# Sheetchanging.net
KiCad netlist of a schematic drawn in Altium Designer
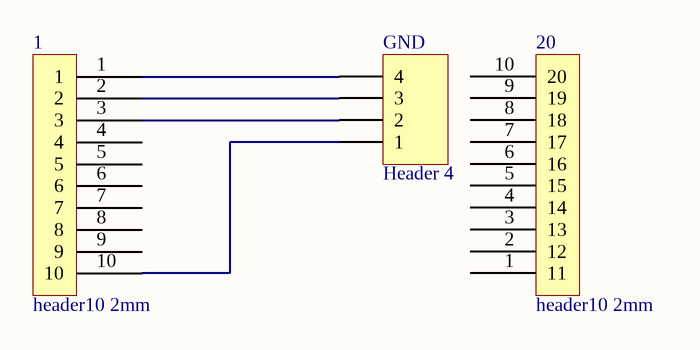
[diagram p0: Sheetchanging.SchDoc]

(export (version "E")
  (design (tool "Eeschema 10.0.6"))
  (components
    (comp (ref "1")
      (value "header10 2mm")
      (footprint "header10 2mm big")
      (libsource (lib "") (part "header10 2mm_1"))
    )
    (comp (ref "20")
      (value "header10 2mm")
      (footprint "header10 2mm big")
      (libsource (lib "My Sch Library") (part "header10 2mm"))
    )
    (comp (ref "GND")
      (value "Header 4")
      (footprint "HDR1X4")
      (description "Header, 4-Pin")
      (fields (field (name "PUBLISHER") "Altium Limited"))
      (libsource (lib "My Sch Library") (part "Header 4"))
    )
  )
  (nets
    (net (code "1") (name "Net-(1-Pad1)") (class "Default")
      (node (ref "1") (pin "1") (pinfunction "1_1") (pintype "passive"))
      (node (ref "GND") (pin "4") (pinfunction "4_4") (pintype "passive"))
    )
    (net (code "2") (name "Net-(1-Pad2)") (class "Default")
      (node (ref "1") (pin "2") (pinfunction "2_2") (pintype "passive"))
      (node (ref "GND") (pin "3") (pinfunction "3_3") (pintype "passive"))
    )
    (net (code "3") (name "Net-(1-Pad3)") (class "Default")
      (node (ref "1") (pin "3") (pinfunction "3_3") (pintype "passive"))
      (node (ref "GND") (pin "2") (pinfunction "2_2") (pintype "passive"))
    )
    (net (code "4") (name "Net-(1-Pad10)") (class "Default")
      (node (ref "1") (pin "10") (pinfunction "10_10") (pintype "passive"))
      (node (ref "GND") (pin "1") (pinfunction "1_1") (pintype "passive"))
    )
    (net (code "5") (name "unconnected-(1-Pad4)") (class "Default")
      (node (ref "1") (pin "4") (pinfunction "4_4") (pintype "passive"))
    )
    (net (code "6") (name "unconnected-(1-Pad5)") (class "Default")
      (node (ref "1") (pin "5") (pinfunction "5_5") (pintype "passive"))
    )
    (net (code "7") (name "unconnected-(1-Pad6)") (class "Default")
      (node (ref "1") (pin "6") (pinfunction "6_6") (pintype "passive"))
    )
    (net (code "8") (name "unconnected-(1-Pad7)") (class "Default")
      (node (ref "1") (pin "7") (pinfunction "7_7") (pintype "passive"))
    )
    (net (code "9") (name "unconnected-(1-Pad8)") (class "Default")
      (node (ref "1") (pin "8") (pinfunction "8_8") (pintype "passive"))
    )
    (net (code "10") (name "unconnected-(1-Pad9)") (class "Default")
      (node (ref "1") (pin "9") (pinfunction "9_9") (pintype "passive"))
    )
    (net (code "11") (name "unconnected-(20-11-Pad1)") (class "Default")
      (node (ref "20") (pin "1") (pinfunction "11_1") (pintype "passive"))
    )
    (net (code "12") (name "unconnected-(20-12-Pad2)") (class "Default")
      (node (ref "20") (pin "2") (pinfunction "12_2") (pintype "passive"))
    )
    (net (code "13") (name "unconnected-(20-13-Pad3)") (class "Default")
      (node (ref "20") (pin "3") (pinfunction "13_3") (pintype "passive"))
    )
    (net (code "14") (name "unconnected-(20-14-Pad4)") (class "Default")
      (node (ref "20") (pin "4") (pinfunction "14_4") (pintype "passive"))
    )
    (net (code "15") (name "unconnected-(20-15-Pad5)") (class "Default")
      (node (ref "20") (pin "5") (pinfunction "15_5") (pintype "passive"))
    )
    (net (code "16") (name "unconnected-(20-16-Pad6)") (class "Default")
      (node (ref "20") (pin "6") (pinfunction "16_6") (pintype "passive"))
    )
    (net (code "17") (name "unconnected-(20-17-Pad7)") (class "Default")
      (node (ref "20") (pin "7") (pinfunction "17_7") (pintype "passive"))
    )
    (net (code "18") (name "unconnected-(20-18-Pad8)") (class "Default")
      (node (ref "20") (pin "8") (pinfunction "18_8") (pintype "passive"))
    )
    (net (code "19") (name "unconnected-(20-19-Pad9)") (class "Default")
      (node (ref "20") (pin "9") (pinfunction "19_9") (pintype "passive"))
    )
    (net (code "20") (name "unconnected-(20-20-Pad10)") (class "Default")
      (node (ref "20") (pin "10") (pinfunction "20_10") (pintype "passive"))
    )
  )
)
